# MEMS_MIC.net
KiCad netlist of a schematic drawn in EAGLE
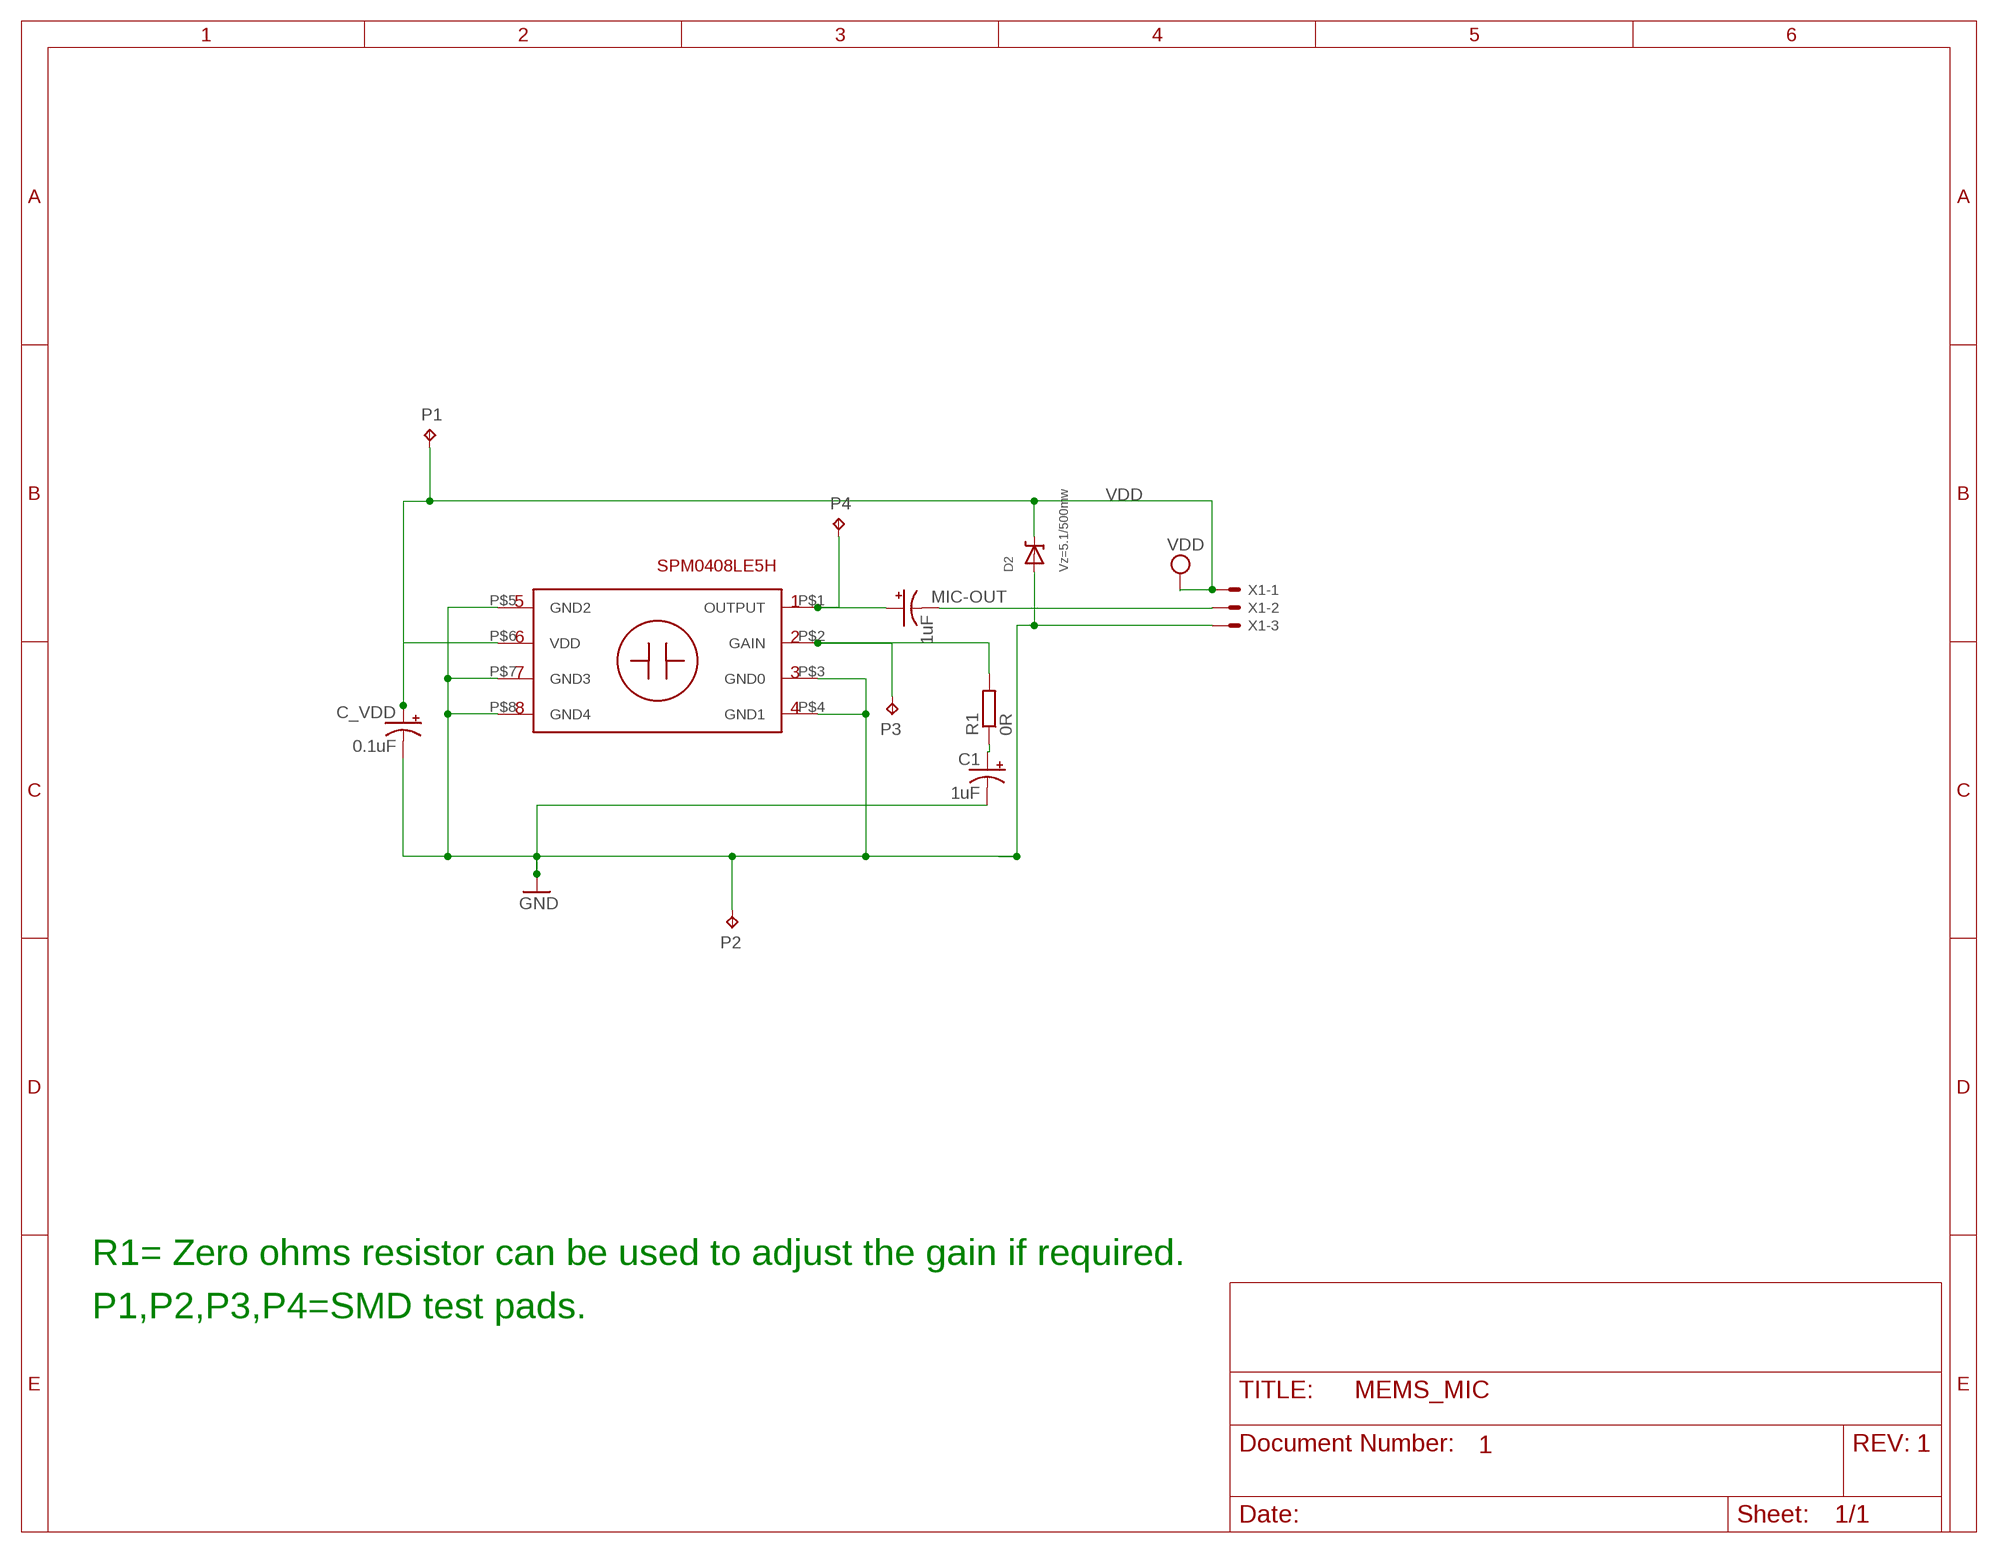
[diagram p0: schematic, sheet 1]

(export (version "E")
  (design (tool "Eeschema 10.0.6"))
  (components
    (comp (ref "C1")
      (value "1uF")
      (footprint "eagle-import:EIA3216-KIT")
      (fields (field (name "MF") "VISHAY SPRAGUE") (field (name "MPN") "293D106X96R3A2TE3"))
      (libsource (lib "eagle-import") (part "CAP_POL1206-KIT"))
    )
    (comp (ref "C_VDD")
      (value "0.1uF")
      (footprint "eagle-import:EIA3216-KIT")
      (fields (field (name "MF") "VISHAY SPRAGUE") (field (name "MPN") "293D106X96R3A2TE3"))
      (libsource (lib "eagle-import") (part "CAP_POL1206-KIT"))
    )
    (comp (ref "D2")
      (value "Vz=5.1/500mw")
      (footprint "eagle-import:SOD-123")
      (libsource (lib "eagle-import") (part "DIODE-ZENERSOD123"))
    )
    (comp (ref "MIC-OUT")
      (value "1uF")
      (footprint "eagle-import:EIA3216-KIT")
      (fields (field (name "MF") "VISHAY SPRAGUE") (field (name "MPN") "293D106X96R3A2TE3"))
      (libsource (lib "eagle-import") (part "CAP_POL1206-KIT"))
    )
    (comp (ref "P1")
      (value "TPB1,27")
      (footprint "eagle-import:B1,27")
      (libsource (lib "eagle-import") (part "TPB1,27"))
    )
    (comp (ref "P2")
      (value "TPB1,27")
      (footprint "eagle-import:B1,27")
      (libsource (lib "eagle-import") (part "TPB1,27"))
    )
    (comp (ref "P3")
      (value "TPB1,27")
      (footprint "eagle-import:B1,27")
      (libsource (lib "eagle-import") (part "TPB1,27"))
    )
    (comp (ref "P4")
      (value "TPB1,27")
      (footprint "eagle-import:B1,27")
      (libsource (lib "eagle-import") (part "TPB1,27"))
    )
    (comp (ref "R1")
      (value "0R")
      (footprint "eagle-import:R0805")
      (libsource (lib "eagle-import") (part "R-EU_R0805"))
    )
    (comp (ref "U2")
      (value "SPM0408LE5H")
      (footprint "eagle-import:SPM0408LE5H-TB")
      (libsource (lib "eagle-import") (part "SPM0408LE5H"))
    )
    (comp (ref "X1")
      (value "87438-03")
      (footprint "eagle-import:87438-03")
      (fields (field (name "MF") "MOLEX"))
      (libsource (lib "eagle-import") (part "87438-03"))
    )
  )
  (nets
    (net (code "1") (name "GND") (class "Default")
      (node (ref "C1") (pin "C") (pinfunction "-_C") (pintype "passive"))
      (node (ref "C_VDD") (pin "C") (pinfunction "-_C") (pintype "passive"))
      (node (ref "D2") (pin "A") (pinfunction "A_A") (pintype "passive"))
      (node (ref "P2") (pin "TP") (pinfunction "TP_TP") (pintype "input"))
      (node (ref "U2") (pin "P$3") (pinfunction "GND0_P$3") (pintype "power_in"))
      (node (ref "U2") (pin "P$4") (pinfunction "GND1_P$4") (pintype "power_in"))
      (node (ref "U2") (pin "P$5") (pinfunction "GND2_P$5") (pintype "power_in"))
      (node (ref "U2") (pin "P$7") (pinfunction "GND3_P$7") (pintype "power_in"))
      (node (ref "U2") (pin "P$8") (pinfunction "GND4_P$8") (pintype "power_in"))
      (node (ref "X1") (pin "3") (pinfunction "S_3") (pintype "passive"))
    )
    (net (code "2") (name "Net-(C1-+)") (class "Default")
      (node (ref "C1") (pin "A") (pinfunction "+_A") (pintype "passive"))
      (node (ref "R1") (pin "1") (pinfunction "1_1") (pintype "passive"))
    )
    (net (code "3") (name "Net-(MIC-OUT-+)") (class "Default")
      (node (ref "MIC-OUT") (pin "A") (pinfunction "+_A") (pintype "passive"))
      (node (ref "P4") (pin "TP") (pinfunction "TP_TP") (pintype "input"))
      (node (ref "U2") (pin "P$1") (pinfunction "OUTPUT_P$1") (pintype "output"))
    )
    (net (code "4") (name "Net-(MIC-OUT--)") (class "Default")
      (node (ref "MIC-OUT") (pin "C") (pinfunction "-_C") (pintype "passive"))
      (node (ref "X1") (pin "2") (pinfunction "S_2") (pintype "passive"))
    )
    (net (code "5") (name "Net-(U2-GAIN)") (class "Default")
      (node (ref "P3") (pin "TP") (pinfunction "TP_TP") (pintype "input"))
      (node (ref "R1") (pin "2") (pinfunction "2_2") (pintype "passive"))
      (node (ref "U2") (pin "P$2") (pinfunction "GAIN_P$2") (pintype "input"))
    )
    (net (code "6") (name "VDD") (class "Default")
      (node (ref "C_VDD") (pin "A") (pinfunction "+_A") (pintype "passive"))
      (node (ref "D2") (pin "C") (pinfunction "C_C") (pintype "passive"))
      (node (ref "P1") (pin "TP") (pinfunction "TP_TP") (pintype "input"))
      (node (ref "U2") (pin "P$6") (pinfunction "VDD_P$6") (pintype "power_in"))
      (node (ref "X1") (pin "1") (pinfunction "S_1") (pintype "passive"))
    )
  )
)
